# SparkFun_MicroMod_ESP32.net
KiCad netlist of a schematic drawn in EAGLE
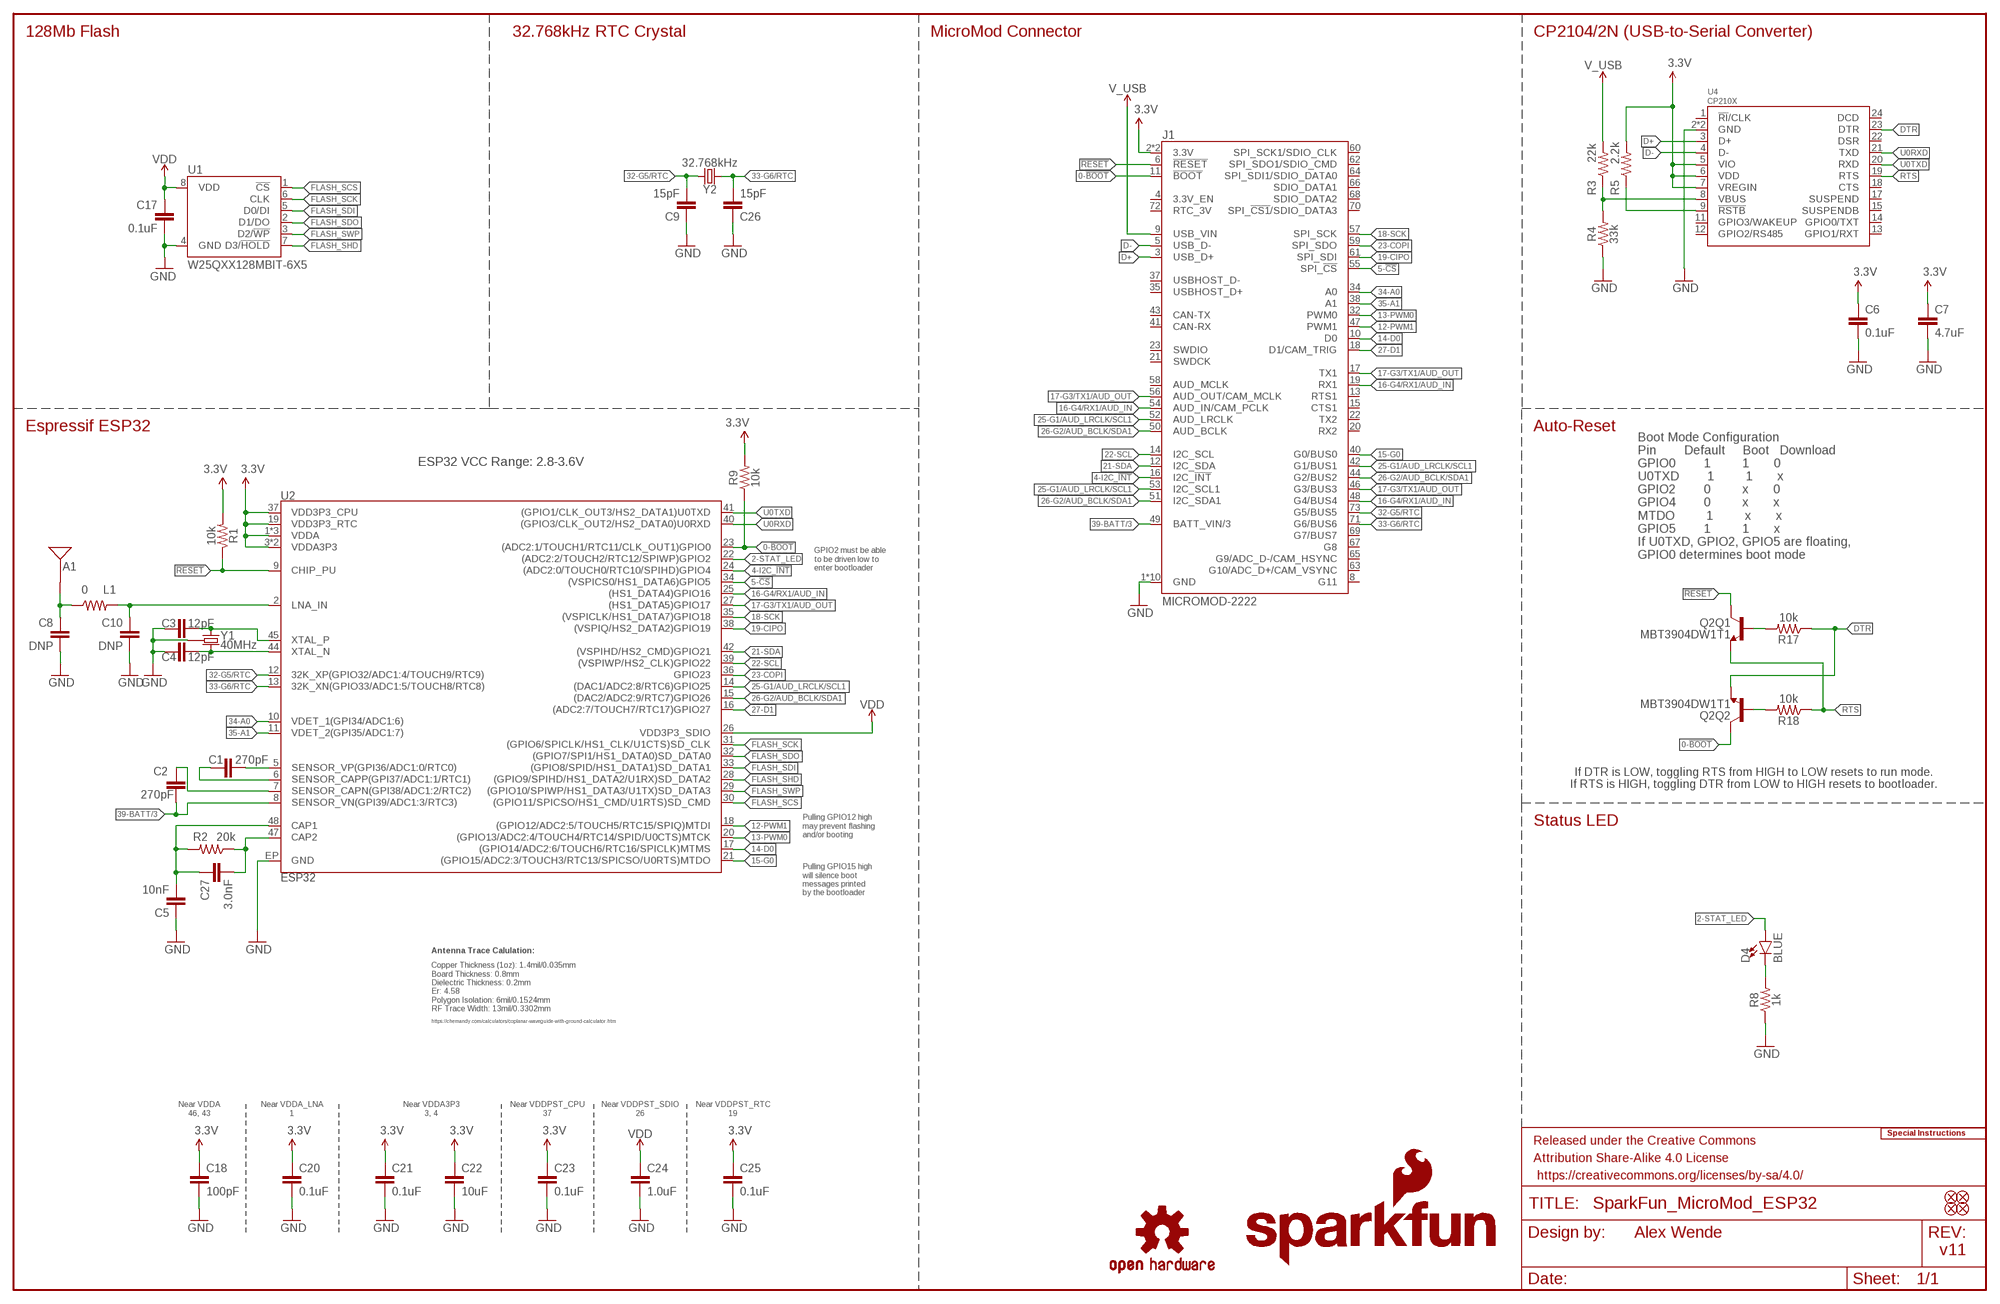
[diagram p0: schematic, sheet 1]

(export (version "E")
  (design (tool "Eeschema 10.0.6"))
  (components
    (comp (ref "A1")
      (value "ANTENNA2.4GHZ-8.0X1.0MM")
      (footprint "eagle-import:ANT-2.4GHZ-8.0X1.0MM")
      (libsource (lib "eagle-import") (part "ANTENNA2.4GHZ-8.0X1.0MM"))
    )
    (comp (ref "C1")
      (value "270pF")
      (footprint "eagle-import:0402-TIGHT")
      (libsource (lib "eagle-import") (part "270PF-0402T-50V-5%"))
    )
    (comp (ref "C2")
      (value "270pF")
      (footprint "eagle-import:0402-TIGHT")
      (libsource (lib "eagle-import") (part "270PF-0402T-50V-5%"))
    )
    (comp (ref "C3")
      (value "12pF")
      (footprint "eagle-import:0402-TIGHT")
      (libsource (lib "eagle-import") (part "12PF-0402T-50V-5%"))
    )
    (comp (ref "C4")
      (value "12pF")
      (footprint "eagle-import:0402-TIGHT")
      (libsource (lib "eagle-import") (part "12PF-0402T-50V-5%"))
    )
    (comp (ref "C5")
      (value "10nF")
      (footprint "eagle-import:0402-TIGHT")
      (libsource (lib "eagle-import") (part "10NF-0402T-25V-10%"))
    )
    (comp (ref "C6")
      (value "0.1uF")
      (footprint "eagle-import:0402-TIGHT")
      (libsource (lib "eagle-import") (part "0.1UF-0402T-16V-10%"))
    )
    (comp (ref "C7")
      (value "4.7uF")
      (footprint "eagle-import:0402-TIGHT")
      (libsource (lib "eagle-import") (part "4.7UF-0402_TIGHT-6.3V-20%-X5R"))
    )
    (comp (ref "C8")
      (value "DNP")
      (footprint "eagle-import:0402-TIGHT")
      (libsource (lib "eagle-import") (part "CAP-0402-TIGHT"))
    )
    (comp (ref "C9")
      (value "15pF")
      (footprint "eagle-import:0402-TIGHT")
      (libsource (lib "eagle-import") (part "15PF-0402T-50V-5%"))
    )
    (comp (ref "C10")
      (value "DNP")
      (footprint "eagle-import:0402-TIGHT")
      (libsource (lib "eagle-import") (part "CAP-0402-TIGHT"))
    )
    (comp (ref "C17")
      (value "0.1uF")
      (footprint "eagle-import:0402-TIGHT")
      (libsource (lib "eagle-import") (part "0.1UF-0402T-16V-10%"))
    )
    (comp (ref "C18")
      (value "100pF")
      (footprint "eagle-import:0402-TIGHT")
      (libsource (lib "eagle-import") (part "100PF-0402T-50V-5%"))
    )
    (comp (ref "C20")
      (value "0.1uF")
      (footprint "eagle-import:0402-TIGHT")
      (libsource (lib "eagle-import") (part "0.1UF-0402T-16V-10%"))
    )
    (comp (ref "C21")
      (value "0.1uF")
      (footprint "eagle-import:0402-TIGHT")
      (libsource (lib "eagle-import") (part "0.1UF-0402T-16V-10%"))
    )
    (comp (ref "C22")
      (value "10uF")
      (footprint "eagle-import:0402-TIGHT")
      (libsource (lib "eagle-import") (part "10UF-0402T-6.3V-20%"))
    )
    (comp (ref "C23")
      (value "0.1uF")
      (footprint "eagle-import:0402-TIGHT")
      (libsource (lib "eagle-import") (part "0.1UF-0402T-16V-10%"))
    )
    (comp (ref "C24")
      (value "1.0uF")
      (footprint "eagle-import:0402-TIGHT")
      (libsource (lib "eagle-import") (part "1.0UF-0402T-16V-10%"))
    )
    (comp (ref "C25")
      (value "0.1uF")
      (footprint "eagle-import:0402-TIGHT")
      (libsource (lib "eagle-import") (part "0.1UF-0402T-16V-10%"))
    )
    (comp (ref "C26")
      (value "15pF")
      (footprint "eagle-import:0402-TIGHT")
      (libsource (lib "eagle-import") (part "15PF-0402T-50V-5%"))
    )
    (comp (ref "C27")
      (value "3.0nF")
      (footprint "eagle-import:0402-TIGHT")
      (libsource (lib "eagle-import") (part "3.0NF-0402T-50V-5%"))
    )
    (comp (ref "D4")
      (value "BLUE")
      (footprint "eagle-import:LED-0603")
      (libsource (lib "eagle-import") (part "LED-BLUE0603"))
    )
    (comp (ref "FD1")
      (value "FIDUCIALUFIDUCIAL")
      (footprint "eagle-import:FIDUCIAL-MICRO")
      (libsource (lib "eagle-import") (part "FIDUCIALUFIDUCIAL"))
    )
    (comp (ref "FD2")
      (value "FIDUCIALUFIDUCIAL")
      (footprint "eagle-import:FIDUCIAL-MICRO")
      (libsource (lib "eagle-import") (part "FIDUCIALUFIDUCIAL"))
    )
    (comp (ref "FD3")
      (value "FIDUCIALUFIDUCIAL")
      (footprint "eagle-import:FIDUCIAL-MICRO")
      (libsource (lib "eagle-import") (part "FIDUCIALUFIDUCIAL"))
    )
    (comp (ref "FD4")
      (value "FIDUCIALUFIDUCIAL")
      (footprint "eagle-import:FIDUCIAL-MICRO")
      (libsource (lib "eagle-import") (part "FIDUCIALUFIDUCIAL"))
    )
    (comp (ref "FRAME1")
      (value "FRAME-LEDGER")
      (footprint "eagle-import:CREATIVE_COMMONS")
      (libsource (lib "eagle-import") (part "FRAME-LEDGER"))
    )
    (comp (ref "J1")
      (value "MICROMOD-2222")
      (footprint "eagle-import:M.2-CARD-E-22")
      (libsource (lib "eagle-import") (part "MICROMOD-2222"))
    )
    (comp (ref "L1")
      (value "0")
      (footprint "eagle-import:0402-TIGHT")
      (libsource (lib "eagle-import") (part "0OHM-0402T-1/10W"))
    )
    (comp (ref "LOGO1")
      (value "SPECIAL_INSTRUCTIONS-ORDERING")
      (footprint "eagle-import:ORDERING_INSTRUCTIONS")
      (libsource (lib "eagle-import") (part "SPECIAL_INSTRUCTIONS-ORDERING"))
    )
    (comp (ref "LOGO2")
      (value "SFE_LOGO_NAME_FLAME.1_INCH")
      (footprint "eagle-import:SFE_LOGO_NAME_FLAME_.1")
      (libsource (lib "eagle-import") (part "SFE_LOGO_NAME_FLAME.1_INCH"))
    )
    (comp (ref "LOGO3")
      (value "OSHW-LOGOS")
      (footprint "eagle-import:OSHW-LOGO-S")
      (libsource (lib "eagle-import") (part "OSHW-LOGOS"))
    )
    (comp (ref "Q2")
      (value "MBT3904DW1T1")
      (footprint "eagle-import:SC70-6")
      (libsource (lib "eagle-import") (part "TRANS_NPN_DUAL-MBT3904DW1T1"))
    )
    (comp (ref "R1")
      (value "10k")
      (footprint "eagle-import:0402-TIGHT")
      (libsource (lib "eagle-import") (part "10KOHM-0402T-1/16W-1%"))
    )
    (comp (ref "R2")
      (value "20k")
      (footprint "eagle-import:0402-TIGHT")
      (libsource (lib "eagle-import") (part "20KOHM-0402T-1/16W-1%"))
    )
    (comp (ref "R3")
      (value "22k")
      (footprint "eagle-import:0402-TIGHT")
      (libsource (lib "eagle-import") (part "22KOHM-0402_TIGHT-1/10W-1%"))
    )
    (comp (ref "R4")
      (value "33k")
      (footprint "eagle-import:0402-TIGHT")
      (libsource (lib "eagle-import") (part "33KOHM-0402T-1/16W-1%"))
    )
    (comp (ref "R5")
      (value "2.2k")
      (footprint "eagle-import:0402-TIGHT")
      (libsource (lib "eagle-import") (part "2.2KOHM-0402T-1/16W-1%"))
    )
    (comp (ref "R8")
      (value "1k")
      (footprint "eagle-import:0402-TIGHT")
      (libsource (lib "eagle-import") (part "1KOHM-0402T-1/16W-1%"))
    )
    (comp (ref "R9")
      (value "10k")
      (footprint "eagle-import:0402-TIGHT")
      (libsource (lib "eagle-import") (part "10KOHM-0402T-1/16W-1%"))
    )
    (comp (ref "R17")
      (value "10k")
      (footprint "eagle-import:0402-TIGHT")
      (libsource (lib "eagle-import") (part "10KOHM-0402T-1/16W-1%"))
    )
    (comp (ref "R18")
      (value "10k")
      (footprint "eagle-import:0402-TIGHT")
      (libsource (lib "eagle-import") (part "10KOHM-0402T-1/16W-1%"))
    )
    (comp (ref "U1")
      (value "W25QXX128MBIT-6X5")
      (footprint "eagle-import:WSON-8-6X5")
      (libsource (lib "eagle-import") (part "W25QXX128MBIT-6X5"))
    )
    (comp (ref "U2")
      (value "ESP32")
      (footprint "eagle-import:QFN48-0.4MM")
      (libsource (lib "eagle-import") (part "ESP32"))
    )
    (comp (ref "U4")
      (value "CP210X")
      (footprint "eagle-import:QFN24")
      (libsource (lib "eagle-import") (part "CP2102N"))
    )
    (comp (ref "Y1")
      (value "40MHz")
      (footprint "eagle-import:CRYSTAL-SMD-2X2.5MM")
      (libsource (lib "eagle-import") (part "CRYSTAL-40MHZ-SMD-2X2.5MM"))
    )
    (comp (ref "Y2")
      (value "32.768kHz")
      (footprint "eagle-import:CRYSTAL-SMD-3.2X1.5MM")
      (libsource (lib "eagle-import") (part "CRYSTAL-32.768KHZSMD-3.2X1.5"))
    )
  )
  (nets
    (net (code "1") (name "/0-~{BOOT}") (class "Default")
      (node (ref "J1") (pin "11") (pinfunction "~{BOOT}_11") (pintype "bidirectional"))
      (node (ref "Q2") (pin "6") (pinfunction "C_6") (pintype "passive"))
      (node (ref "R9") (pin "1") (pinfunction "1_1") (pintype "passive"))
      (node (ref "U2") (pin "23") (pinfunction "(ADC2:1/TOUCH1/RTC11/CLK_OUT1)GPIO0_23") (pintype "bidirectional"))
    )
    (net (code "2") (name "/4-I2C_~{INT}") (class "Default")
      (node (ref "J1") (pin "16") (pinfunction "I2C_~{INT}_16") (pintype "bidirectional"))
      (node (ref "U2") (pin "24") (pinfunction "(ADC2:0/TOUCH0/RTC10/SPIHD)GPIO4_24") (pintype "bidirectional"))
    )
    (net (code "3") (name "/5-~{CS}") (class "Default")
      (node (ref "J1") (pin "55") (pinfunction "SPI_~{CS}_55") (pintype "bidirectional"))
      (node (ref "U2") (pin "34") (pinfunction "(VSPICS0/HS1_DATA6)GPIO5_34") (pintype "bidirectional"))
    )
    (net (code "4") (name "/~{RESET}") (class "Default")
      (node (ref "J1") (pin "6") (pinfunction "~{RESET}_6") (pintype "bidirectional"))
      (node (ref "Q2") (pin "3") (pinfunction "C_3") (pintype "passive"))
      (node (ref "R1") (pin "1") (pinfunction "1_1") (pintype "passive"))
      (node (ref "U2") (pin "9") (pinfunction "CHIP_PU_9") (pintype "bidirectional"))
    )
    (net (code "5") (name "2-STAT_LED") (class "Default")
      (node (ref "D4") (pin "A") (pinfunction "A_A") (pintype "passive"))
      (node (ref "U2") (pin "22") (pinfunction "(ADC2:2/TOUCH2/RTC12/SPIWP)GPIO2_22") (pintype "bidirectional"))
    )
    (net (code "6") (name "3.3V") (class "Default")
      (node (ref "C18") (pin "1") (pinfunction "1_1") (pintype "passive"))
      (node (ref "C20") (pin "1") (pinfunction "1_1") (pintype "passive"))
      (node (ref "C21") (pin "1") (pinfunction "1_1") (pintype "passive"))
      (node (ref "C22") (pin "1") (pinfunction "1_1") (pintype "passive"))
      (node (ref "C23") (pin "1") (pinfunction "1_1") (pintype "passive"))
      (node (ref "C25") (pin "1") (pinfunction "1_1") (pintype "passive"))
      (node (ref "C6") (pin "1") (pinfunction "1_1") (pintype "passive"))
      (node (ref "C7") (pin "1") (pinfunction "1_1") (pintype "passive"))
      (node (ref "J1") (pin "2") (pinfunction "3.3V_2") (pintype "bidirectional"))
      (node (ref "J1") (pin "74") (pinfunction "3.3V_74") (pintype "bidirectional"))
      (node (ref "R1") (pin "2") (pinfunction "2_2") (pintype "passive"))
      (node (ref "R5") (pin "2") (pinfunction "2_2") (pintype "passive"))
      (node (ref "R9") (pin "2") (pinfunction "2_2") (pintype "passive"))
      (node (ref "U2") (pin "1") (pinfunction "VDDA_1") (pintype "bidirectional"))
      (node (ref "U2") (pin "19") (pinfunction "VDD3P3_RTC_19") (pintype "bidirectional"))
      (node (ref "U2") (pin "3") (pinfunction "VDDA3P3_3") (pintype "bidirectional"))
      (node (ref "U2") (pin "37") (pinfunction "VDD3P3_CPU_37") (pintype "bidirectional"))
      (node (ref "U2") (pin "4") (pinfunction "VDDA3P3_4") (pintype "bidirectional"))
      (node (ref "U2") (pin "43") (pinfunction "VDDA_43") (pintype "bidirectional"))
      (node (ref "U2") (pin "46") (pinfunction "VDDA_46") (pintype "bidirectional"))
      (node (ref "U4") (pin "5") (pinfunction "VIO_5") (pintype "bidirectional"))
      (node (ref "U4") (pin "6") (pinfunction "VDD_6") (pintype "bidirectional"))
      (node (ref "U4") (pin "7") (pinfunction "VREGIN_7") (pintype "bidirectional"))
    )
    (net (code "7") (name "12-PWM1") (class "Default")
      (node (ref "J1") (pin "47") (pinfunction "PWM1_47") (pintype "bidirectional"))
      (node (ref "U2") (pin "18") (pinfunction "(GPIO12/ADC2:5/TOUCH5/RTC15/SPIQ)MTDI_18") (pintype "bidirectional"))
    )
    (net (code "8") (name "13-PWM0") (class "Default")
      (node (ref "J1") (pin "32") (pinfunction "PWM0_32") (pintype "bidirectional"))
      (node (ref "U2") (pin "20") (pinfunction "(GPIO13/ADC2:4/TOUCH4/RTC14/SPID/U0CTS)MTCK_20") (pintype "bidirectional"))
    )
    (net (code "9") (name "14-D0") (class "Default")
      (node (ref "J1") (pin "10") (pinfunction "D0_10") (pintype "bidirectional"))
      (node (ref "U2") (pin "17") (pinfunction "(GPIO14/ADC2:6/TOUCH6/RTC16/SPICLK)MTMS_17") (pintype "bidirectional"))
    )
    (net (code "10") (name "15-G0") (class "Default")
      (node (ref "J1") (pin "40") (pinfunction "G0/BUS0_40") (pintype "bidirectional"))
      (node (ref "U2") (pin "21") (pinfunction "(GPIO15/ADC2:3/TOUCH3/RTC13/SPICSO/U0RTS)MTDO_21") (pintype "bidirectional"))
    )
    (net (code "11") (name "16-G4{slash}RX1{slash}AUD_IN") (class "Default")
      (node (ref "J1") (pin "19") (pinfunction "RX1_19") (pintype "bidirectional"))
      (node (ref "J1") (pin "48") (pinfunction "G4/BUS4_48") (pintype "bidirectional"))
      (node (ref "J1") (pin "54") (pinfunction "AUD_IN/CAM_PCLK_54") (pintype "bidirectional"))
      (node (ref "U2") (pin "25") (pinfunction "(HS1_DATA4)GPIO16_25") (pintype "bidirectional"))
    )
    (net (code "12") (name "17-G3{slash}TX1{slash}AUD_OUT") (class "Default")
      (node (ref "J1") (pin "17") (pinfunction "TX1_17") (pintype "bidirectional"))
      (node (ref "J1") (pin "46") (pinfunction "G3/BUS3_46") (pintype "bidirectional"))
      (node (ref "J1") (pin "56") (pinfunction "AUD_OUT/CAM_MCLK_56") (pintype "bidirectional"))
      (node (ref "U2") (pin "27") (pinfunction "(HS1_DATA5)GPIO17_27") (pintype "bidirectional"))
    )
    (net (code "13") (name "18-SCK") (class "Default")
      (node (ref "J1") (pin "57") (pinfunction "SPI_SCK_57") (pintype "bidirectional"))
      (node (ref "U2") (pin "35") (pinfunction "(VSPICLK/HS1_DATA7)GPIO18_35") (pintype "bidirectional"))
    )
    (net (code "14") (name "19-CIPO") (class "Default")
      (node (ref "J1") (pin "61") (pinfunction "SPI_SDI_61") (pintype "bidirectional"))
      (node (ref "U2") (pin "38") (pinfunction "(VSPIQ/HS2_DATA2)GPIO19_38") (pintype "bidirectional"))
    )
    (net (code "15") (name "21-SDA") (class "Default")
      (node (ref "J1") (pin "12") (pinfunction "I2C_SDA_12") (pintype "bidirectional"))
      (node (ref "U2") (pin "42") (pinfunction "(VSPIHD/HS2_CMD)GPIO21_42") (pintype "bidirectional"))
    )
    (net (code "16") (name "22-SCL") (class "Default")
      (node (ref "J1") (pin "14") (pinfunction "I2C_SCL_14") (pintype "bidirectional"))
      (node (ref "U2") (pin "39") (pinfunction "(VSPIWP/HS2_CLK)GPIO22_39") (pintype "bidirectional"))
    )
    (net (code "17") (name "23-COPI") (class "Default")
      (node (ref "J1") (pin "59") (pinfunction "SPI_SDO_59") (pintype "bidirectional"))
      (node (ref "U2") (pin "36") (pinfunction "GPIO23_36") (pintype "bidirectional"))
    )
    (net (code "18") (name "25-G1{slash}AUD_LRCLK{slash}SCL1") (class "Default")
      (node (ref "J1") (pin "42") (pinfunction "G1/BUS1_42") (pintype "bidirectional"))
      (node (ref "J1") (pin "52") (pinfunction "AUD_LRCLK_52") (pintype "bidirectional"))
      (node (ref "J1") (pin "53") (pinfunction "I2C_SCL1_53") (pintype "bidirectional"))
      (node (ref "U2") (pin "14") (pinfunction "(DAC1/ADC2:8/RTC6)GPIO25_14") (pintype "bidirectional"))
    )
    (net (code "19") (name "26-G2{slash}AUD_BCLK{slash}SDA1") (class "Default")
      (node (ref "J1") (pin "44") (pinfunction "G2/BUS2_44") (pintype "bidirectional"))
      (node (ref "J1") (pin "50") (pinfunction "AUD_BCLK_50") (pintype "bidirectional"))
      (node (ref "J1") (pin "51") (pinfunction "I2C_SDA1_51") (pintype "bidirectional"))
      (node (ref "U2") (pin "15") (pinfunction "(DAC2/ADC2:9/RTC7)GPIO26_15") (pintype "bidirectional"))
    )
    (net (code "20") (name "27-D1") (class "Default")
      (node (ref "J1") (pin "18") (pinfunction "D1/CAM_TRIG_18") (pintype "bidirectional"))
      (node (ref "U2") (pin "16") (pinfunction "(ADC2:7/TOUCH7/RTC17)GPIO27_16") (pintype "bidirectional"))
    )
    (net (code "21") (name "32-G5{slash}RTC") (class "Default")
      (node (ref "C9") (pin "2") (pinfunction "2_2") (pintype "passive"))
      (node (ref "J1") (pin "73") (pinfunction "G5/BUS5_73") (pintype "bidirectional"))
      (node (ref "U2") (pin "12") (pinfunction "32K_XP(GPIO32/ADC1:4/TOUCH9/RTC9)_12") (pintype "bidirectional"))
      (node (ref "Y2") (pin "P$1") (pinfunction "1_P$1") (pintype "passive"))
    )
    (net (code "22") (name "33-G6{slash}RTC") (class "Default")
      (node (ref "C26") (pin "2") (pinfunction "2_2") (pintype "passive"))
      (node (ref "J1") (pin "71") (pinfunction "G6/BUS6_71") (pintype "bidirectional"))
      (node (ref "U2") (pin "13") (pinfunction "32K_XN(GPIO33/ADC1:5/TOUCH8/RTC8)_13") (pintype "bidirectional"))
      (node (ref "Y2") (pin "P$2") (pinfunction "2_P$2") (pintype "passive"))
    )
    (net (code "23") (name "34-A0") (class "Default")
      (node (ref "J1") (pin "34") (pinfunction "A0_34") (pintype "bidirectional"))
      (node (ref "U2") (pin "10") (pinfunction "VDET_1(GPI34/ADC1:6)_10") (pintype "bidirectional"))
    )
    (net (code "24") (name "35-A1") (class "Default")
      (node (ref "J1") (pin "38") (pinfunction "A1_38") (pintype "bidirectional"))
      (node (ref "U2") (pin "11") (pinfunction "VDET_2(GPI35/ADC1:7)_11") (pintype "bidirectional"))
    )
    (net (code "25") (name "39-BATT{slash}3") (class "Default")
      (node (ref "C2") (pin "2") (pinfunction "2_2") (pintype "passive"))
      (node (ref "J1") (pin "49") (pinfunction "BATT_VIN/3_49") (pintype "bidirectional"))
      (node (ref "U2") (pin "8") (pinfunction "SENSOR_VN(GPI39/ADC1:3/RTC3)_8") (pintype "bidirectional"))
    )
    (net (code "26") (name "D+") (class "Default")
      (node (ref "J1") (pin "3") (pinfunction "USB_D+_3") (pintype "bidirectional"))
      (node (ref "U4") (pin "3") (pinfunction "D+_3") (pintype "bidirectional"))
    )
    (net (code "27") (name "D-") (class "Default")
      (node (ref "J1") (pin "5") (pinfunction "USB_D-_5") (pintype "bidirectional"))
      (node (ref "U4") (pin "4") (pinfunction "D-_4") (pintype "bidirectional"))
    )
    (net (code "28") (name "DTR") (class "Default")
      (node (ref "Q2") (pin "1") (pinfunction "E_1") (pintype "passive"))
      (node (ref "R17") (pin "1") (pinfunction "1_1") (pintype "passive"))
      (node (ref "U4") (pin "23") (pinfunction "DTR_23") (pintype "bidirectional"))
    )
    (net (code "29") (name "FLASH_SCK") (class "Default")
      (node (ref "U1") (pin "6") (pinfunction "CLK_6") (pintype "bidirectional"))
      (node (ref "U2") (pin "31") (pinfunction "(GPIO6/SPICLK/HS1_CLK/U1CTS)SD_CLK_31") (pintype "bidirectional"))
    )
    (net (code "30") (name "FLASH_SCS") (class "Default")
      (node (ref "U1") (pin "1") (pinfunction "~{CS}_1") (pintype "bidirectional"))
      (node (ref "U2") (pin "30") (pinfunction "(GPIO11/SPICSO/HS1_CMD/U1RTS)SD_CMD_30") (pintype "bidirectional"))
    )
    (net (code "31") (name "FLASH_SDI") (class "Default")
      (node (ref "U1") (pin "5") (pinfunction "D0/DI_5") (pintype "bidirectional"))
      (node (ref "U2") (pin "33") (pinfunction "(GPIO8/SPID/HS1_DATA1)SD_DATA1_33") (pintype "bidirectional"))
    )
    (net (code "32") (name "FLASH_SDO") (class "Default")
      (node (ref "U1") (pin "2") (pinfunction "D1/DO_2") (pintype "bidirectional"))
      (node (ref "U2") (pin "32") (pinfunction "(GPIO7/SPI1/HS1_DATA0)SD_DATA0_32") (pintype "bidirectional"))
    )
    (net (code "33") (name "FLASH_SHD") (class "Default")
      (node (ref "U1") (pin "7") (pinfunction "D3/~{HOLD}_7") (pintype "bidirectional"))
      (node (ref "U2") (pin "28") (pinfunction "(GPIO9/SPIHD/HS1_DATA2/U1RX)SD_DATA2_28") (pintype "bidirectional"))
    )
    (net (code "34") (name "FLASH_SWP") (class "Default")
      (node (ref "U1") (pin "3") (pinfunction "D2/~{WP}_3") (pintype "bidirectional"))
      (node (ref "U2") (pin "29") (pinfunction "(GPIO10/SPIWP/HS1_DATA3/U1TX)SD_DATA3_29") (pintype "bidirectional"))
    )
    (net (code "35") (name "GND") (class "Default")
      (node (ref "C10") (pin "2") (pinfunction "2_2") (pintype "passive"))
      (node (ref "C17") (pin "2") (pinfunction "2_2") (pintype "passive"))
      (node (ref "C18") (pin "2") (pinfunction "2_2") (pintype "passive"))
      (node (ref "C20") (pin "2") (pinfunction "2_2") (pintype "passive"))
      (node (ref "C21") (pin "2") (pinfunction "2_2") (pintype "passive"))
      (node (ref "C22") (pin "2") (pinfunction "2_2") (pintype "passive"))
      (node (ref "C23") (pin "2") (pinfunction "2_2") (pintype "passive"))
      (node (ref "C24") (pin "2") (pinfunction "2_2") (pintype "passive"))
      (node (ref "C25") (pin "2") (pinfunction "2_2") (pintype "passive"))
      (node (ref "C26") (pin "1") (pinfunction "1_1") (pintype "passive"))
      (node (ref "C3") (pin "1") (pinfunction "1_1") (pintype "passive"))
      (node (ref "C4") (pin "1") (pinfunction "1_1") (pintype "passive"))
      (node (ref "C5") (pin "1") (pinfunction "1_1") (pintype "passive"))
      (node (ref "C6") (pin "2") (pinfunction "2_2") (pintype "passive"))
      (node (ref "C7") (pin "2") (pinfunction "2_2") (pintype "passive"))
      (node (ref "C8") (pin "2") (pinfunction "2_2") (pintype "passive"))
      (node (ref "C9") (pin "1") (pinfunction "1_1") (pintype "passive"))
      (node (ref "J1") (pin "1") (pinfunction "GND_1") (pintype "bidirectional"))
      (node (ref "J1") (pin "33") (pinfunction "GND_33") (pintype "bidirectional"))
      (node (ref "J1") (pin "36") (pinfunction "GND_36") (pintype "bidirectional"))
      (node (ref "J1") (pin "39") (pinfunction "GND_39") (pintype "bidirectional"))
      (node (ref "J1") (pin "45") (pinfunction "GND_45") (pintype "bidirectional"))
      (node (ref "J1") (pin "7") (pinfunction "GND_7") (pintype "bidirectional"))
      (node (ref "J1") (pin "75") (pinfunction "GND_75") (pintype "bidirectional"))
      (node (ref "J1") (pin "GND1") (pinfunction "GND_GND1") (pintype "bidirectional"))
      (node (ref "J1") (pin "GND2") (pinfunction "GND_GND2") (pintype "bidirectional"))
      (node (ref "J1") (pin "GND3") (pinfunction "GND_GND3") (pintype "bidirectional"))
      (node (ref "R4") (pin "1") (pinfunction "1_1") (pintype "passive"))
      (node (ref "R8") (pin "1") (pinfunction "1_1") (pintype "passive"))
      (node (ref "U1") (pin "4") (pinfunction "GND_4") (pintype "bidirectional"))
      (node (ref "U2") (pin "EP") (pinfunction "GND_EP") (pintype "bidirectional"))
      (node (ref "U4") (pin "2") (pinfunction "GND_2") (pintype "bidirectional"))
      (node (ref "U4") (pin "PAD") (pinfunction "GND_PAD") (pintype "bidirectional"))
      (node (ref "Y1") (pin "P2") (pinfunction "GND_P2") (pintype "power_in"))
      (node (ref "Y1") (pin "P4") (pinfunction "GND_P4") (pintype "power_in"))
    )
    (net (code "36") (name "Net-(A1-SIGNAL)") (class "Default")
      (node (ref "A1") (pin "FEED") (pinfunction "SIGNAL_FEED") (pintype "bidirectional"))
      (node (ref "C8") (pin "1") (pinfunction "1_1") (pintype "passive"))
      (node (ref "L1") (pin "1") (pinfunction "1_1") (pintype "passive"))
    )
    (net (code "37") (name "Net-(D4-PadC)") (class "Default")
      (node (ref "D4") (pin "C") (pinfunction "C_C") (pintype "passive"))
      (node (ref "R8") (pin "2") (pinfunction "2_2") (pintype "passive"))
    )
    (net (code "38") (name "Net-(Q2A-B)") (class "Default")
      (node (ref "Q2") (pin "5") (pinfunction "B_5") (pintype "passive"))
      (node (ref "R17") (pin "2") (pinfunction "2_2") (pintype "passive"))
    )
    (net (code "39") (name "Net-(Q2B-B)") (class "Default")
      (node (ref "Q2") (pin "2") (pinfunction "B_2") (pintype "passive"))
      (node (ref "R18") (pin "2") (pinfunction "2_2") (pintype "passive"))
    )
    (net (code "40") (name "Net-(U2-CAP1)") (class "Default")
      (node (ref "C27") (pin "1") (pinfunction "1_1") (pintype "passive"))
      (node (ref "C5") (pin "2") (pinfunction "2_2") (pintype "passive"))
      (node (ref "R2") (pin "2") (pinfunction "2_2") (pintype "passive"))
      (node (ref "U2") (pin "48") (pinfunction "CAP1_48") (pintype "bidirectional"))
    )
    (net (code "41") (name "Net-(U2-CAP2)") (class "Default")
      (node (ref "C27") (pin "2") (pinfunction "2_2") (pintype "passive"))
      (node (ref "R2") (pin "1") (pinfunction "1_1") (pintype "passive"))
      (node (ref "U2") (pin "47") (pinfunction "CAP2_47") (pintype "bidirectional"))
    )
    (net (code "42") (name "Net-(U2-LNA_IN)") (class "Default")
      (node (ref "C10") (pin "1") (pinfunction "1_1") (pintype "passive"))
      (node (ref "L1") (pin "2") (pinfunction "2_2") (pintype "passive"))
      (node (ref "U2") (pin "2") (pinfunction "LNA_IN_2") (pintype "bidirectional"))
    )
    (net (code "43") (name "Net-(U2-SENSOR_CAPN(GPI38{slash}ADC1:2{slash}RTC2))") (class "Default")
      (node (ref "C2") (pin "1") (pinfunction "1_1") (pintype "passive"))
      (node (ref "U2") (pin "7") (pinfunction "SENSOR_CAPN(GPI38/ADC1:2/RTC2)_7") (pintype "bidirectional"))
    )
    (net (code "44") (name "Net-(U2-SENSOR_CAPP(GPI37{slash}ADC1:1{slash}RTC1))") (class "Default")
      (node (ref "C1") (pin "1") (pinfunction "1_1") (pintype "passive"))
      (node (ref "U2") (pin "6") (pinfunction "SENSOR_CAPP(GPI37/ADC1:1/RTC1)_6") (pintype "bidirectional"))
    )
    (net (code "45") (name "Net-(U2-SENSOR_VP(GPI36{slash}ADC1:0{slash}RTC0))") (class "Default")
      (node (ref "C1") (pin "2") (pinfunction "2_2") (pintype "passive"))
      (node (ref "U2") (pin "5") (pinfunction "SENSOR_VP(GPI36/ADC1:0/RTC0)_5") (pintype "bidirectional"))
    )
    (net (code "46") (name "Net-(U2-XTAL_N)") (class "Default")
      (node (ref "C4") (pin "2") (pinfunction "2_2") (pintype "passive"))
      (node (ref "U2") (pin "44") (pinfunction "XTAL_N_44") (pintype "bidirectional"))
      (node (ref "Y1") (pin "P3") (pinfunction "2_P3") (pintype "passive"))
    )
    (net (code "47") (name "Net-(U2-XTAL_P)") (class "Default")
      (node (ref "C3") (pin "2") (pinfunction "2_2") (pintype "passive"))
      (node (ref "U2") (pin "45") (pinfunction "XTAL_P_45") (pintype "bidirectional"))
      (node (ref "Y1") (pin "P1") (pinfunction "1_P1") (pintype "passive"))
    )
    (net (code "48") (name "Net-(U4-VBUS)") (class "Default")
      (node (ref "R3") (pin "1") (pinfunction "1_1") (pintype "passive"))
      (node (ref "R4") (pin "2") (pinfunction "2_2") (pintype "passive"))
      (node (ref "U4") (pin "8") (pinfunction "VBUS_8") (pintype "bidirectional"))
    )
    (net (code "49") (name "Net-(U4-~{RSTB})") (class "Default")
      (node (ref "R5") (pin "1") (pinfunction "1_1") (pintype "passive"))
      (node (ref "U4") (pin "9") (pinfunction "~{RSTB}_9") (pintype "bidirectional"))
    )
    (net (code "50") (name "RTS") (class "Default")
      (node (ref "Q2") (pin "4") (pinfunction "E_4") (pintype "passive"))
      (node (ref "R18") (pin "1") (pinfunction "1_1") (pintype "passive"))
      (node (ref "U4") (pin "19") (pinfunction "RTS_19") (pintype "bidirectional"))
    )
    (net (code "51") (name "U0RXD") (class "Default")
      (node (ref "U2") (pin "40") (pinfunction "(GPIO3/CLK_OUT2/HS2_DATA0)U0RXD_40") (pintype "bidirectional"))
      (node (ref "U4") (pin "21") (pinfunction "TXD_21") (pintype "bidirectional"))
    )
    (net (code "52") (name "U0TXD") (class "Default")
      (node (ref "U2") (pin "41") (pinfunction "(GPIO1/CLK_OUT3/HS2_DATA1)U0TXD_41") (pintype "bidirectional"))
      (node (ref "U4") (pin "20") (pinfunction "RXD_20") (pintype "bidirectional"))
    )
    (net (code "53") (name "VDD") (class "Default")
      (node (ref "C17") (pin "1") (pinfunction "1_1") (pintype "passive"))
      (node (ref "C24") (pin "1") (pinfunction "1_1") (pintype "passive"))
      (node (ref "U1") (pin "8") (pinfunction "VDD_8") (pintype "bidirectional"))
      (node (ref "U2") (pin "26") (pinfunction "VDD3P3_SDIO_26") (pintype "bidirectional"))
    )
    (net (code "54") (name "V_USB") (class "Default")
      (node (ref "J1") (pin "9") (pinfunction "USB_VIN_9") (pintype "bidirectional"))
      (node (ref "R3") (pin "2") (pinfunction "2_2") (pintype "passive"))
    )
    (net (code "55") (name "unconnected-(J1-3.3V_EN-Pad4)") (class "Default")
      (node (ref "J1") (pin "4") (pinfunction "3.3V_EN_4") (pintype "bidirectional"))
    )
    (net (code "56") (name "unconnected-(J1-AUD_MCLK-Pad58)") (class "Default")
      (node (ref "J1") (pin "58") (pinfunction "AUD_MCLK_58") (pintype "bidirectional"))
    )
    (net (code "57") (name "unconnected-(J1-CAN-RX-Pad41)") (class "Default")
      (node (ref "J1") (pin "41") (pinfunction "CAN-RX_41") (pintype "bidirectional"))
    )
    (net (code "58") (name "unconnected-(J1-CAN-TX-Pad43)") (class "Default")
      (node (ref "J1") (pin "43") (pinfunction "CAN-TX_43") (pintype "bidirectional"))
    )
    (net (code "59") (name "unconnected-(J1-CTS1-Pad15)") (class "Default")
      (node (ref "J1") (pin "15") (pinfunction "CTS1_15") (pintype "bidirectional"))
    )
    (net (code "60") (name "unconnected-(J1-G7{slash}BUS7-Pad69)") (class "Default")
      (node (ref "J1") (pin "69") (pinfunction "G7/BUS7_69") (pintype "bidirectional"))
    )
    (net (code "61") (name "unconnected-(J1-G8-Pad67)") (class "Default")
      (node (ref "J1") (pin "67") (pinfunction "G8_67") (pintype "bidirectional"))
    )
    (net (code "62") (name "unconnected-(J1-G9{slash}ADC_D-{slash}CAM_HSYNC-Pad65)") (class "Default")
      (node (ref "J1") (pin "65") (pinfunction "G9/ADC_D-/CAM_HSYNC_65") (pintype "bidirectional"))
    )
    (net (code "63") (name "unconnected-(J1-G10{slash}ADC_D+{slash}CAM_VSYNC-Pad63)") (class "Default")
      (node (ref "J1") (pin "63") (pinfunction "G10/ADC_D+/CAM_VSYNC_63") (pintype "bidirectional"))
    )
    (net (code "64") (name "unconnected-(J1-G11-Pad8)") (class "Default")
      (node (ref "J1") (pin "8") (pinfunction "G11_8") (pintype "bidirectional"))
    )
    (net (code "65") (name "unconnected-(J1-RTC_3V-Pad72)") (class "Default")
      (node (ref "J1") (pin "72") (pinfunction "RTC_3V_72") (pintype "bidirectional"))
    )
    (net (code "66") (name "unconnected-(J1-RTS1-Pad13)") (class "Default")
      (node (ref "J1") (pin "13") (pinfunction "RTS1_13") (pintype "bidirectional"))
    )
    (net (code "67") (name "unconnected-(J1-RX2-Pad20)") (class "Default")
      (node (ref "J1") (pin "20") (pinfunction "RX2_20") (pintype "bidirectional"))
    )
    (net (code "68") (name "unconnected-(J1-SDIO_DATA1-Pad66)") (class "Default")
      (node (ref "J1") (pin "66") (pinfunction "SDIO_DATA1_66") (pintype "bidirectional"))
    )
    (net (code "69") (name "unconnected-(J1-SDIO_DATA2-Pad68)") (class "Default")
      (node (ref "J1") (pin "68") (pinfunction "SDIO_DATA2_68") (pintype "bidirectional"))
    )
    (net (code "70") (name "unconnected-(J1-SPI_SCK1{slash}SDIO_CLK-Pad60)") (class "Default")
      (node (ref "J1") (pin "60") (pinfunction "SPI_SCK1/SDIO_CLK_60") (pintype "bidirectional"))
    )
    (net (code "71") (name "unconnected-(J1-SPI_SDI1{slash}SDIO_DATA0-Pad64)") (class "Default")
      (node (ref "J1") (pin "64") (pinfunction "SPI_SDI1/SDIO_DATA0_64") (pintype "bidirectional"))
    )
    (net (code "72") (name "unconnected-(J1-SPI_SDO1{slash}SDIO_CMD-Pad62)") (class "Default")
      (node (ref "J1") (pin "62") (pinfunction "SPI_SDO1/SDIO_CMD_62") (pintype "bidirectional"))
    )
    (net (code "73") (name "unconnected-(J1-SPI_~{CS1}{slash}SDIO_DATA3-Pad70)") (class "Default")
      (node (ref "J1") (pin "70") (pinfunction "SPI_~{CS1}/SDIO_DATA3_70") (pintype "bidirectional"))
    )
    (net (code "74") (name "unconnected-(J1-SWDCK-Pad21)") (class "Default")
      (node (ref "J1") (pin "21") (pinfunction "SWDCK_21") (pintype "bidirectional"))
    )
    (net (code "75") (name "unconnected-(J1-SWDIO-Pad23)") (class "Default")
      (node (ref "J1") (pin "23") (pinfunction "SWDIO_23") (pintype "bidirectional"))
    )
    (net (code "76") (name "unconnected-(J1-TX2-Pad22)") (class "Default")
      (node (ref "J1") (pin "22") (pinfunction "TX2_22") (pintype "bidirectional"))
    )
    (net (code "77") (name "unconnected-(J1-USBHOST_D+-Pad35)") (class "Default")
      (node (ref "J1") (pin "35") (pinfunction "USBHOST_D+_35") (pintype "bidirectional"))
    )
    (net (code "78") (name "unconnected-(J1-USBHOST_D--Pad37)") (class "Default")
      (node (ref "J1") (pin "37") (pinfunction "USBHOST_D-_37") (pintype "bidirectional"))
    )
    (net (code "79") (name "unconnected-(U4-CTS-Pad18)") (class "Default")
      (node (ref "U4") (pin "18") (pinfunction "CTS_18") (pintype "bidirectional"))
    )
    (net (code "80") (name "unconnected-(U4-DCD-Pad24)") (class "Default")
      (node (ref "U4") (pin "24") (pinfunction "DCD_24") (pintype "bidirectional"))
    )
    (net (code "81") (name "unconnected-(U4-DSR-Pad22)") (class "Default")
      (node (ref "U4") (pin "22") (pinfunction "DSR_22") (pintype "bidirectional"))
    )
    (net (code "82") (name "unconnected-(U4-GPIO0{slash}TXT-Pad14)") (class "Default")
      (node (ref "U4") (pin "14") (pinfunction "GPIO0/TXT_14") (pintype "bidirectional"))
    )
    (net (code "83") (name "unconnected-(U4-GPIO1{slash}RXT-Pad13)") (class "Default")
      (node (ref "U4") (pin "13") (pinfunction "GPIO1/RXT_13") (pintype "bidirectional"))
    )
    (net (code "84") (name "unconnected-(U4-GPIO2{slash}RS485-Pad12)") (class "Default")
      (node (ref "U4") (pin "12") (pinfunction "GPIO2/RS485_12") (pintype "bidirectional"))
    )
    (net (code "85") (name "unconnected-(U4-GPIO3{slash}WAKEUP-Pad11)") (class "Default")
      (node (ref "U4") (pin "11") (pinfunction "GPIO3/WAKEUP_11") (pintype "bidirectional"))
    )
    (net (code "86") (name "unconnected-(U4-SUSPEND-Pad17)") (class "Default")
      (node (ref "U4") (pin "17") (pinfunction "SUSPEND_17") (pintype "bidirectional"))
    )
    (net (code "87") (name "unconnected-(U4-SUSPENDB-Pad15)") (class "Default")
      (node (ref "U4") (pin "15") (pinfunction "SUSPENDB_15") (pintype "bidirectional"))
    )
    (net (code "88") (name "unconnected-(U4-~{RI}{slash}CLK-Pad1)") (class "Default")
      (node (ref "U4") (pin "1") (pinfunction "~{RI}/CLK_1") (pintype "bidirectional"))
    )
  )
)
